# Zwischenplatine.net
KiCad netlist of a schematic drawn in EAGLE
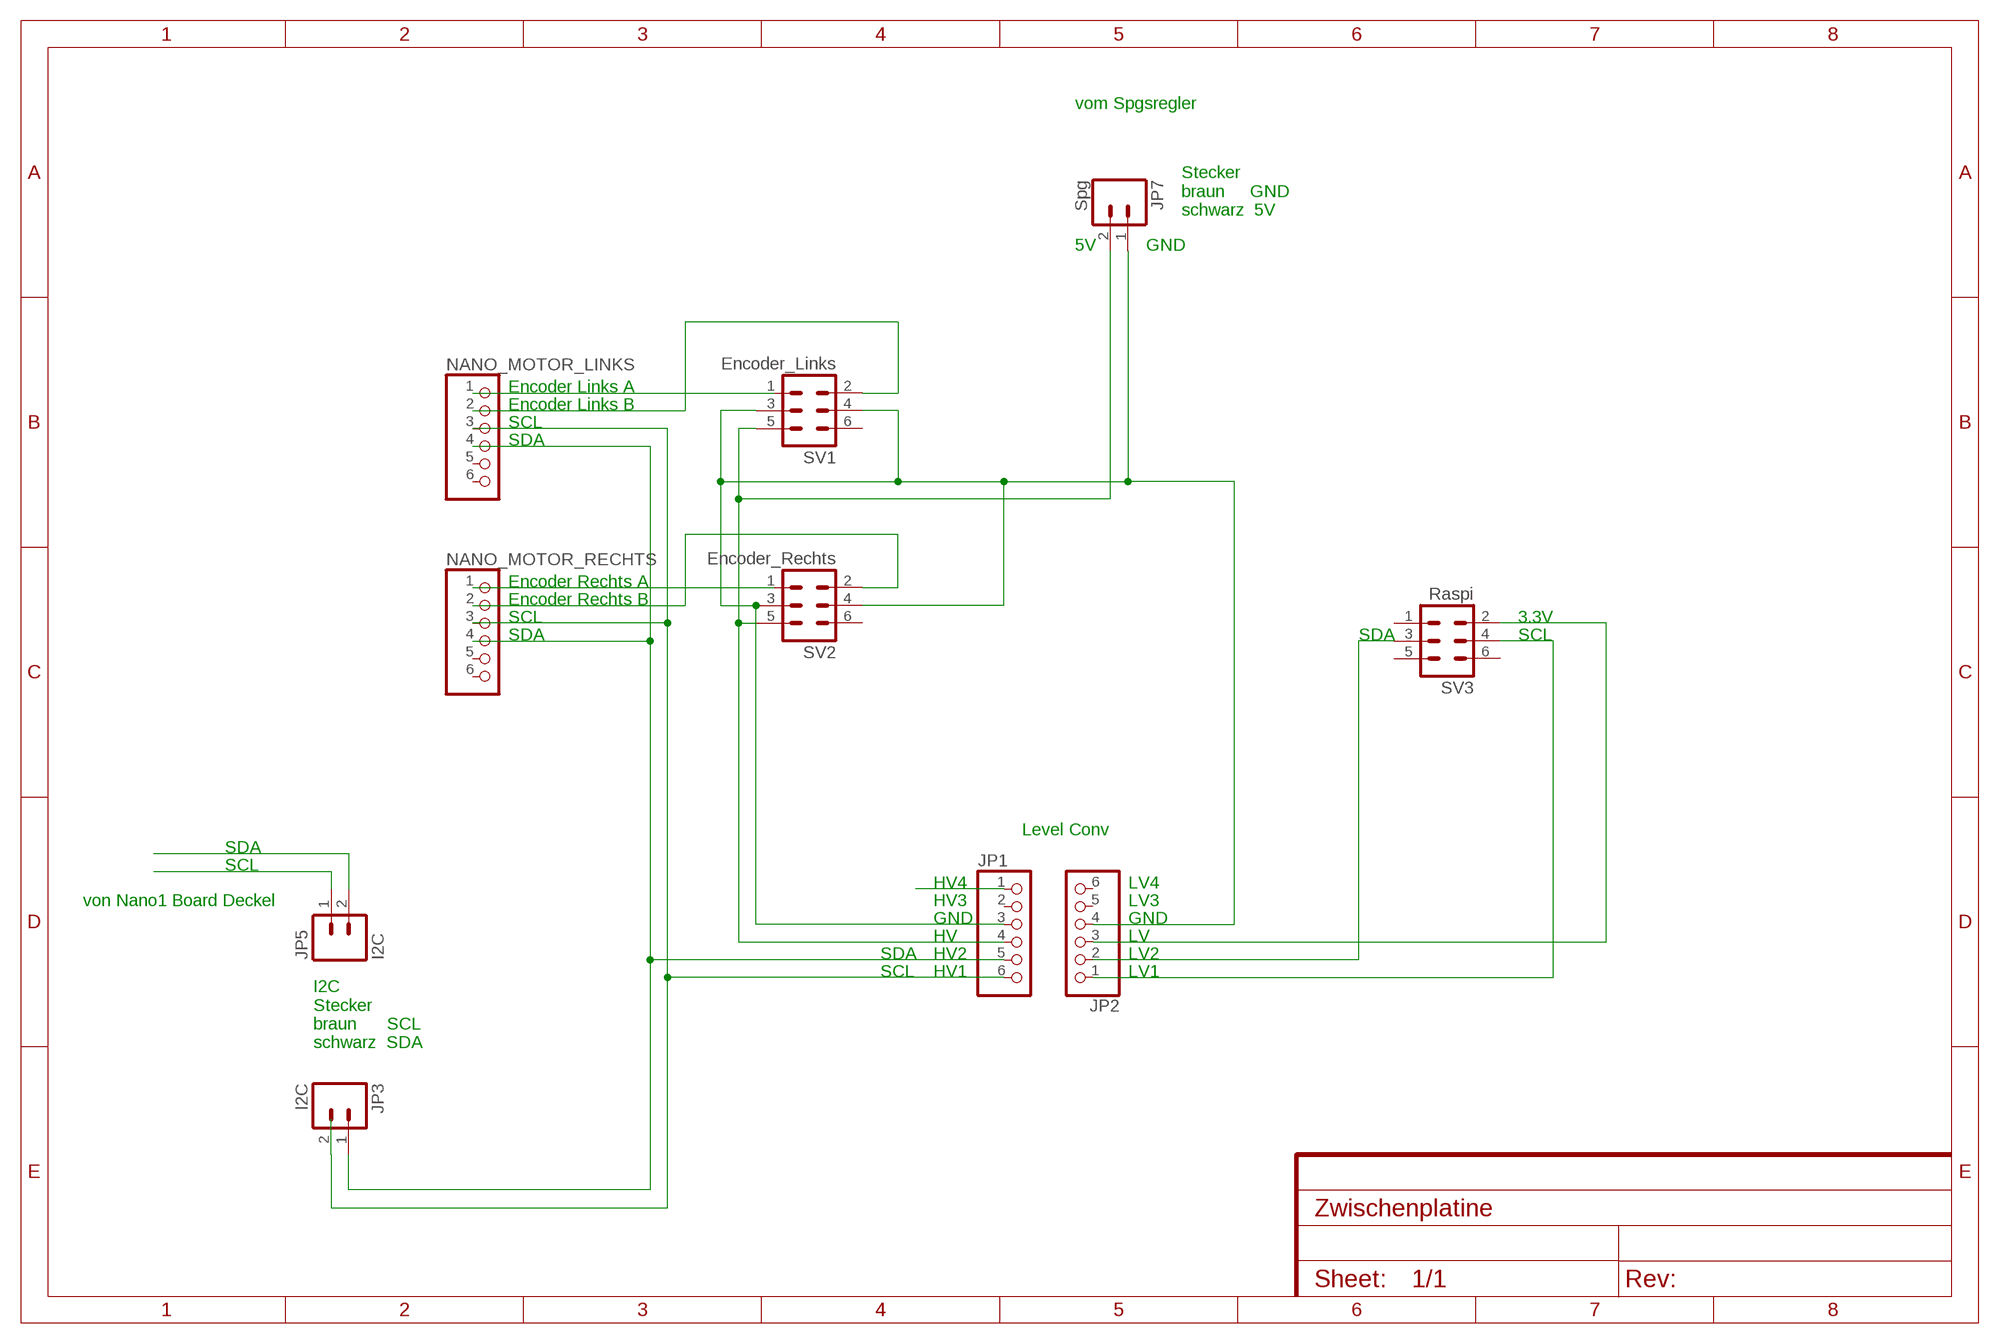
[diagram p0: schematic, sheet 1]

(export (version "E")
  (design (tool "Eeschema 10.0.6"))
  (components
    (comp (ref "JP1")
      (value "PINHD-1X6B")
      (footprint "eagle-import:1X06-BIG")
      (libsource (lib "eagle-import") (part "PINHD-1X6B"))
    )
    (comp (ref "JP2")
      (value "PINHD-1X6B")
      (footprint "eagle-import:1X06-BIG")
      (libsource (lib "eagle-import") (part "PINHD-1X6B"))
    )
    (comp (ref "JP3")
      (value "I2C")
      (footprint "eagle-import:JST-2-SMD")
      (libsource (lib "eagle-import") (part "M02-JST-2MM-SMT"))
    )
    (comp (ref "JP5")
      (value "I2C")
      (footprint "eagle-import:JST-2-SMD")
      (libsource (lib "eagle-import") (part "M02-JST-2MM-SMT"))
    )
    (comp (ref "JP7")
      (value "Spg")
      (footprint "eagle-import:JST-2-SMD")
      (libsource (lib "eagle-import") (part "M02-JST-2MM-SMT"))
    )
    (comp (ref "NANO_MOTOR_LINKS")
      (value "PINHD-1X6B")
      (footprint "eagle-import:1X06-BIG")
      (libsource (lib "eagle-import") (part "PINHD-1X6B"))
    )
    (comp (ref "NANO_MOTOR_RECHTS")
      (value "PINHD-1X6B")
      (footprint "eagle-import:1X06-BIG")
      (libsource (lib "eagle-import") (part "PINHD-1X6B"))
    )
    (comp (ref "SV1")
      (value "Encoder_Links")
      (footprint "eagle-import:ML6")
      (libsource (lib "eagle-import") (part "ML6"))
    )
    (comp (ref "SV2")
      (value "Encoder_Rechts")
      (footprint "eagle-import:ML6")
      (libsource (lib "eagle-import") (part "ML6"))
    )
    (comp (ref "SV3")
      (value "Raspi")
      (footprint "eagle-import:ML6")
      (libsource (lib "eagle-import") (part "ML6"))
    )
  )
  (nets
    (net (code "1") (name "Net-(JP2-Pad1)") (class "Default")
      (node (ref "JP2") (pin "1") (pinfunction "1_1") (pintype "passive"))
      (node (ref "SV3") (pin "4") (pinfunction "4_4") (pintype "passive"))
    )
    (net (code "2") (name "Net-(JP2-Pad2)") (class "Default")
      (node (ref "JP2") (pin "2") (pinfunction "2_2") (pintype "passive"))
      (node (ref "SV3") (pin "3") (pinfunction "3_3") (pintype "passive"))
    )
    (net (code "3") (name "Net-(JP2-Pad3)") (class "Default")
      (node (ref "JP2") (pin "3") (pinfunction "3_3") (pintype "passive"))
      (node (ref "SV3") (pin "2") (pinfunction "2_2") (pintype "passive"))
    )
    (net (code "4") (name "Net-(JP3-1)") (class "Default")
      (node (ref "JP1") (pin "6") (pinfunction "6_6") (pintype "passive"))
      (node (ref "JP3") (pin "2") (pinfunction "1_2") (pintype "passive"))
      (node (ref "NANO_MOTOR_LINKS") (pin "3") (pinfunction "3_3") (pintype "passive"))
      (node (ref "NANO_MOTOR_RECHTS") (pin "3") (pinfunction "3_3") (pintype "passive"))
    )
    (net (code "5") (name "Net-(JP3-2)") (class "Default")
      (node (ref "JP1") (pin "5") (pinfunction "5_5") (pintype "passive"))
      (node (ref "JP3") (pin "1") (pinfunction "2_1") (pintype "passive"))
      (node (ref "NANO_MOTOR_LINKS") (pin "4") (pinfunction "4_4") (pintype "passive"))
      (node (ref "NANO_MOTOR_RECHTS") (pin "4") (pinfunction "4_4") (pintype "passive"))
    )
    (net (code "6") (name "Net-(JP7-1)") (class "Default")
      (node (ref "JP1") (pin "4") (pinfunction "4_4") (pintype "passive"))
      (node (ref "JP7") (pin "2") (pinfunction "1_2") (pintype "passive"))
      (node (ref "SV1") (pin "5") (pinfunction "5_5") (pintype "passive"))
      (node (ref "SV2") (pin "5") (pinfunction "5_5") (pintype "passive"))
    )
    (net (code "7") (name "Net-(JP7-2)") (class "Default")
      (node (ref "JP1") (pin "3") (pinfunction "3_3") (pintype "passive"))
      (node (ref "JP2") (pin "4") (pinfunction "4_4") (pintype "passive"))
      (node (ref "JP7") (pin "1") (pinfunction "2_1") (pintype "passive"))
      (node (ref "SV1") (pin "3") (pinfunction "3_3") (pintype "passive"))
      (node (ref "SV1") (pin "4") (pinfunction "4_4") (pintype "passive"))
      (node (ref "SV2") (pin "3") (pinfunction "3_3") (pintype "passive"))
      (node (ref "SV2") (pin "4") (pinfunction "4_4") (pintype "passive"))
    )
    (net (code "8") (name "Net-(NANO_MOTOR_LINKS-Pad2)") (class "Default")
      (node (ref "NANO_MOTOR_LINKS") (pin "2") (pinfunction "2_2") (pintype "passive"))
      (node (ref "SV1") (pin "2") (pinfunction "2_2") (pintype "passive"))
    )
    (net (code "9") (name "Net-(NANO_MOTOR_RECHTS-Pad1)") (class "Default")
      (node (ref "NANO_MOTOR_RECHTS") (pin "1") (pinfunction "1_1") (pintype "passive"))
      (node (ref "SV2") (pin "1") (pinfunction "1_1") (pintype "passive"))
    )
    (net (code "10") (name "Net-(NANO_MOTOR_RECHTS-Pad2)") (class "Default")
      (node (ref "NANO_MOTOR_RECHTS") (pin "2") (pinfunction "2_2") (pintype "passive"))
      (node (ref "SV2") (pin "2") (pinfunction "2_2") (pintype "passive"))
    )
    (net (code "11") (name "unconnected-(JP1-Pad1)") (class "Default")
      (node (ref "JP1") (pin "1") (pinfunction "1_1") (pintype "passive"))
    )
    (net (code "12") (name "unconnected-(JP1-Pad2)") (class "Default")
      (node (ref "JP1") (pin "2") (pinfunction "2_2") (pintype "passive"))
    )
    (net (code "13") (name "unconnected-(JP2-Pad5)") (class "Default")
      (node (ref "JP2") (pin "5") (pinfunction "5_5") (pintype "passive"))
    )
    (net (code "14") (name "unconnected-(JP2-Pad6)") (class "Default")
      (node (ref "JP2") (pin "6") (pinfunction "6_6") (pintype "passive"))
    )
    (net (code "15") (name "unconnected-(JP5-1-Pad2)") (class "Default")
      (node (ref "JP5") (pin "2") (pinfunction "1_2") (pintype "passive"))
    )
    (net (code "16") (name "unconnected-(JP5-2-Pad1)") (class "Default")
      (node (ref "JP5") (pin "1") (pinfunction "2_1") (pintype "passive"))
    )
    (net (code "17") (name "unconnected-(NANO_MOTOR_LINKS-Pad1)") (class "Default")
      (node (ref "NANO_MOTOR_LINKS") (pin "1") (pinfunction "1_1") (pintype "passive"))
    )
    (net (code "18") (name "unconnected-(NANO_MOTOR_LINKS-Pad5)") (class "Default")
      (node (ref "NANO_MOTOR_LINKS") (pin "5") (pinfunction "5_5") (pintype "passive"))
    )
    (net (code "19") (name "unconnected-(NANO_MOTOR_LINKS-Pad6)") (class "Default")
      (node (ref "NANO_MOTOR_LINKS") (pin "6") (pinfunction "6_6") (pintype "passive"))
    )
    (net (code "20") (name "unconnected-(NANO_MOTOR_RECHTS-Pad5)") (class "Default")
      (node (ref "NANO_MOTOR_RECHTS") (pin "5") (pinfunction "5_5") (pintype "passive"))
    )
    (net (code "21") (name "unconnected-(NANO_MOTOR_RECHTS-Pad6)") (class "Default")
      (node (ref "NANO_MOTOR_RECHTS") (pin "6") (pinfunction "6_6") (pintype "passive"))
    )
    (net (code "22") (name "unconnected-(SV1-Pad1)") (class "Default")
      (node (ref "SV1") (pin "1") (pinfunction "1_1") (pintype "passive"))
    )
    (net (code "23") (name "unconnected-(SV1-Pad6)") (class "Default")
      (node (ref "SV1") (pin "6") (pinfunction "6_6") (pintype "passive"))
    )
    (net (code "24") (name "unconnected-(SV2-Pad6)") (class "Default")
      (node (ref "SV2") (pin "6") (pinfunction "6_6") (pintype "passive"))
    )
    (net (code "25") (name "unconnected-(SV3-Pad1)") (class "Default")
      (node (ref "SV3") (pin "1") (pinfunction "1_1") (pintype "passive"))
    )
    (net (code "26") (name "unconnected-(SV3-Pad5)") (class "Default")
      (node (ref "SV3") (pin "5") (pinfunction "5_5") (pintype "passive"))
    )
    (net (code "27") (name "unconnected-(SV3-Pad6)") (class "Default")
      (node (ref "SV3") (pin "6") (pinfunction "6_6") (pintype "passive"))
    )
  )
)
